# PMOD.net
KiCad netlist of a schematic drawn in Altium Designer
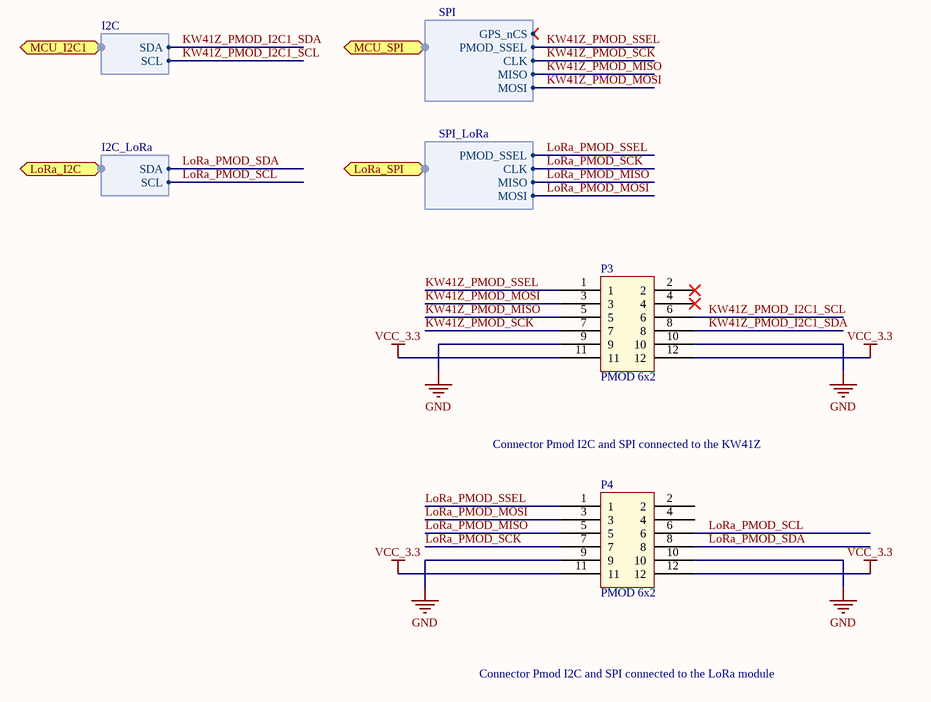
[diagram p0: PMOD.SchDoc]

(export (version "E")
  (design (tool "Eeschema 10.0.6"))
  (components
    (comp (ref "P3")
      (value "PMOD 6x2")
      (footprint "PMOD SMD Header 6x2")
      (description "Header, 6-Pin, Dual row")
      (libsource (lib "HEPIA Vault") (part "Header 6X2"))
    )
    (comp (ref "P4")
      (value "PMOD 6x2")
      (footprint "PMOD SMD Header 6x2")
      (description "Header, 6-Pin, Dual row")
      (libsource (lib "HEPIA Vault") (part "Header 6X2"))
    )
  )
  (nets
    (net (code "5") (name "/KW41Z_PMOD_I2C1_SCL") (class "Default")
      (node (ref "P3") (pin "6") (pinfunction "6_6") (pintype "passive"))
    )
    (net (code "6") (name "/KW41Z_PMOD_I2C1_SDA") (class "Default")
      (node (ref "P3") (pin "8") (pinfunction "8_8") (pintype "passive"))
    )
    (net (code "7") (name "/KW41Z_PMOD_MISO") (class "Default")
      (node (ref "P3") (pin "5") (pinfunction "5_5") (pintype "passive"))
    )
    (net (code "8") (name "/KW41Z_PMOD_MOSI") (class "Default")
      (node (ref "P3") (pin "3") (pinfunction "3_3") (pintype "passive"))
    )
    (net (code "9") (name "/KW41Z_PMOD_SCK") (class "Default")
      (node (ref "P3") (pin "7") (pinfunction "7_7") (pintype "passive"))
    )
    (net (code "10") (name "/KW41Z_PMOD_SSEL") (class "Default")
      (node (ref "P3") (pin "1") (pinfunction "1_1") (pintype "passive"))
    )
    (net (code "11") (name "/LoRa_PMOD_MISO") (class "Default")
      (node (ref "P4") (pin "5") (pinfunction "5_5") (pintype "passive"))
    )
    (net (code "12") (name "/LoRa_PMOD_MOSI") (class "Default")
      (node (ref "P4") (pin "3") (pinfunction "3_3") (pintype "passive"))
    )
    (net (code "13") (name "/LoRa_PMOD_SCK") (class "Default")
      (node (ref "P4") (pin "7") (pinfunction "7_7") (pintype "passive"))
    )
    (net (code "14") (name "/LoRa_PMOD_SCL") (class "Default")
      (node (ref "P4") (pin "6") (pinfunction "6_6") (pintype "passive"))
    )
    (net (code "15") (name "/LoRa_PMOD_SDA") (class "Default")
      (node (ref "P4") (pin "8") (pinfunction "8_8") (pintype "passive"))
    )
    (net (code "16") (name "/LoRa_PMOD_SSEL") (class "Default")
      (node (ref "P4") (pin "1") (pinfunction "1_1") (pintype "passive"))
    )
    (net (code "21") (name "GND") (class "Default")
      (node (ref "P3") (pin "10") (pinfunction "10_10") (pintype "passive"))
      (node (ref "P3") (pin "9") (pinfunction "9_9") (pintype "passive"))
      (node (ref "P4") (pin "10") (pinfunction "10_10") (pintype "passive"))
      (node (ref "P4") (pin "9") (pinfunction "9_9") (pintype "passive"))
    )
    (net (code "22") (name "VCC_3.3") (class "Default")
      (node (ref "P3") (pin "11") (pinfunction "11_11") (pintype "passive"))
      (node (ref "P3") (pin "12") (pinfunction "12_12") (pintype "passive"))
      (node (ref "P4") (pin "11") (pinfunction "11_11") (pintype "passive"))
      (node (ref "P4") (pin "12") (pinfunction "12_12") (pintype "passive"))
    )
    (net (code "23") (name "unconnected-(P3-Pad2)") (class "Default")
      (node (ref "P3") (pin "2") (pinfunction "2_2") (pintype "passive+no_connect"))
    )
    (net (code "24") (name "unconnected-(P3-Pad4)") (class "Default")
      (node (ref "P3") (pin "4") (pinfunction "4_4") (pintype "passive+no_connect"))
    )
    (net (code "25") (name "unconnected-(P4-Pad2)") (class "Default")
      (node (ref "P4") (pin "2") (pinfunction "2_2") (pintype "passive"))
    )
    (net (code "26") (name "unconnected-(P4-Pad4)") (class "Default")
      (node (ref "P4") (pin "4") (pinfunction "4_4") (pintype "passive"))
    )
  )
)
